# a.net
KiCad netlist of a schematic drawn in EAGLE
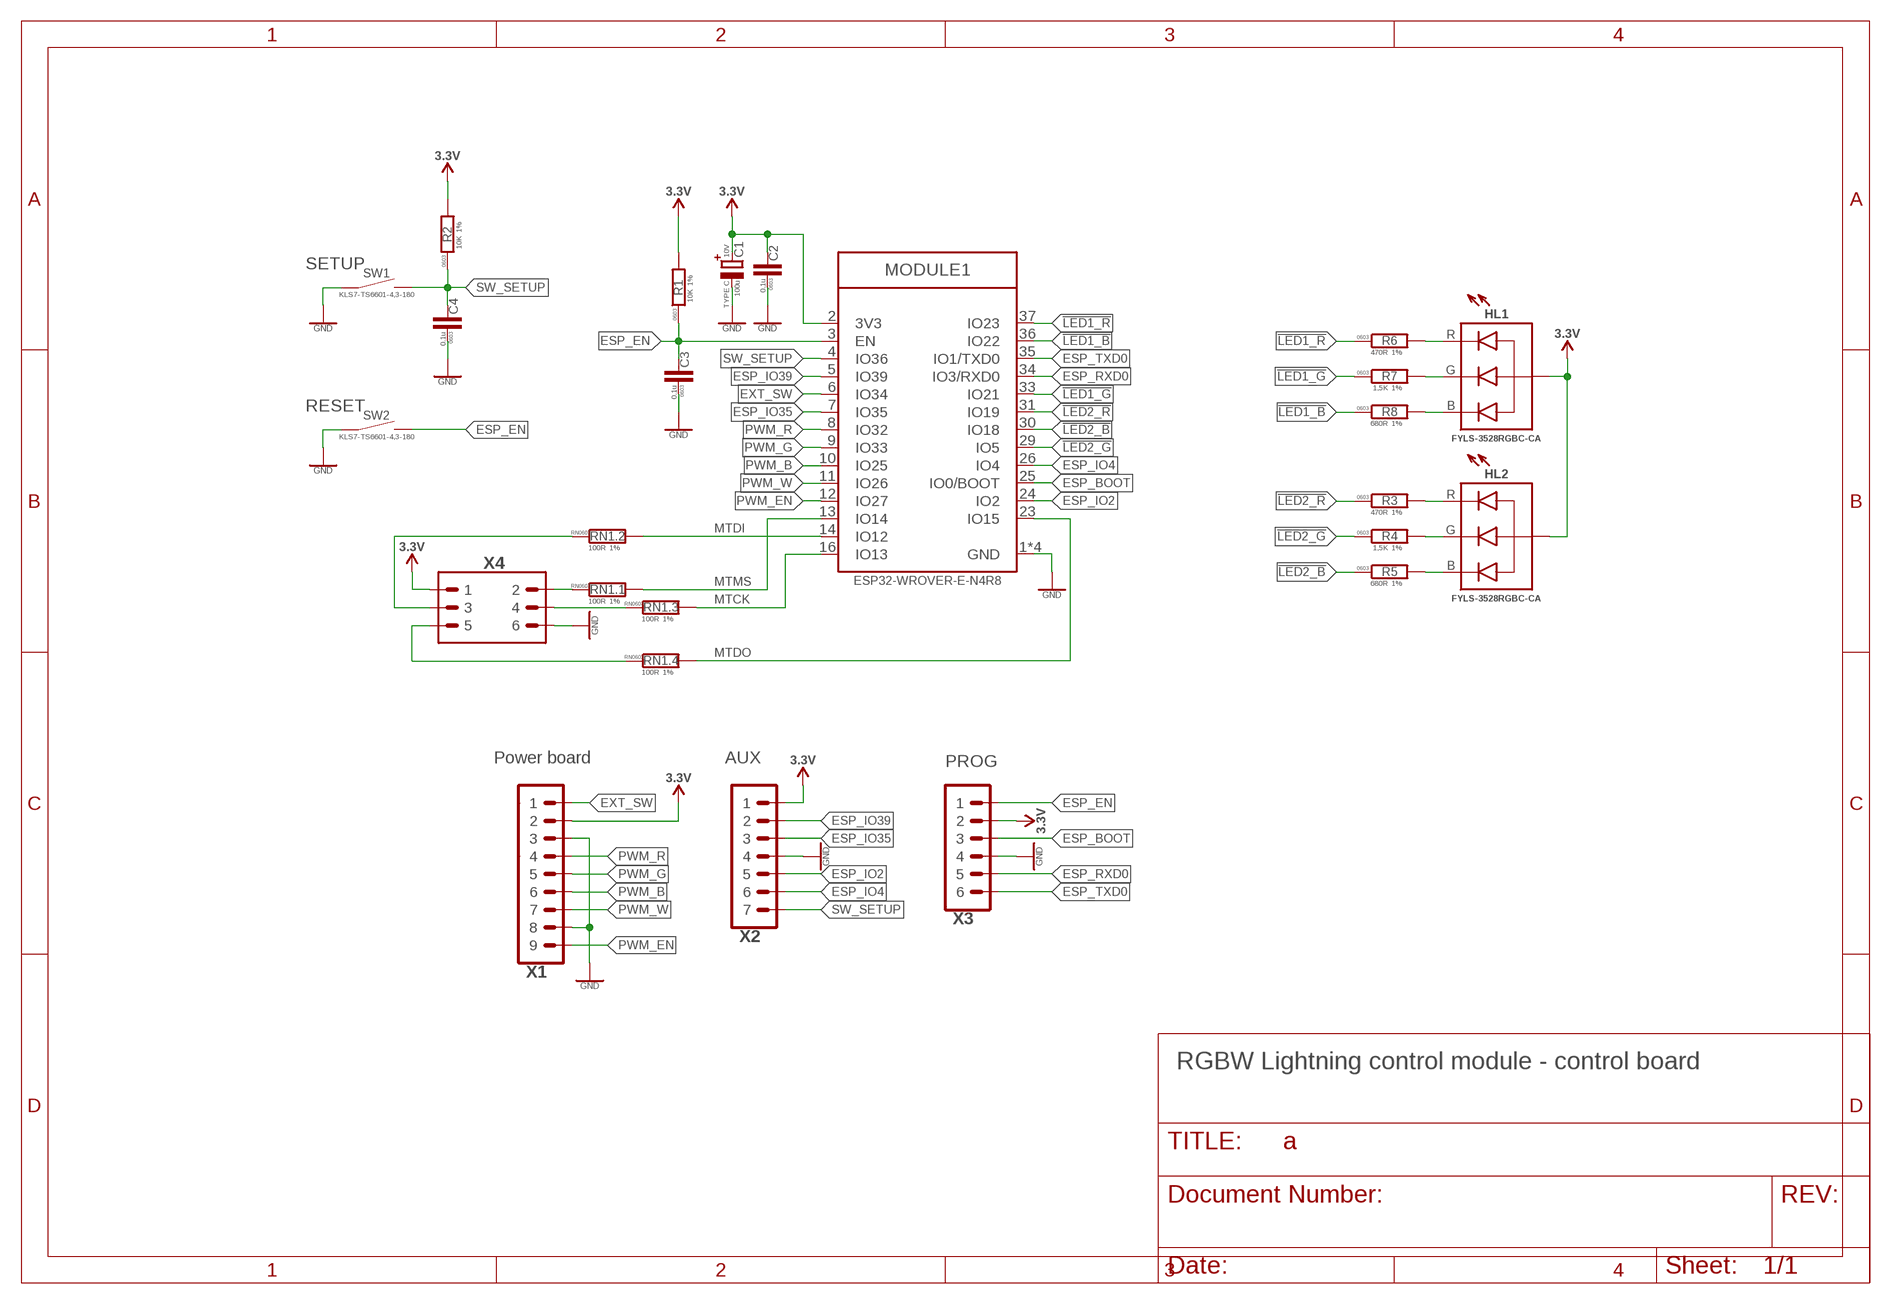
[diagram p0: schematic, sheet 1]

(export (version "E")
  (design (tool "Eeschema 10.0.6"))
  (components
    (comp (ref "C1")
      (value "100u")
      (footprint "eagle-import:CTANT_TYPE_C")
      (fields (field (name "PACKAGE") "TYPE C") (field (name "VOLTAGE") "10V"))
      (libsource (lib "eagle-import") (part "CPOL-TANT-TYPE-C"))
    )
    (comp (ref "C2")
      (value "0.1u")
      (footprint "eagle-import:C0603")
      (fields (field (name "PACKAGE") "0603"))
      (libsource (lib "eagle-import") (part "C-0603"))
    )
    (comp (ref "C3")
      (value "0.1u")
      (footprint "eagle-import:C0603")
      (fields (field (name "PACKAGE") "0603"))
      (libsource (lib "eagle-import") (part "C-0603"))
    )
    (comp (ref "C4")
      (value "0.1u")
      (footprint "eagle-import:C0603")
      (fields (field (name "PACKAGE") "0603"))
      (libsource (lib "eagle-import") (part "C-0603"))
    )
    (comp (ref "HL1")
      (value "LED_RGB-3528")
      (footprint "eagle-import:LED3528")
      (fields (field (name "MANF#") "FYLS-3528RGBC-CA") (field (name "MANF") "Foryard"))
      (libsource (lib "eagle-import") (part "LED_RGB-3528"))
    )
    (comp (ref "HL2")
      (value "LED_RGB-3528")
      (footprint "eagle-import:LED3528")
      (fields (field (name "MANF#") "FYLS-3528RGBC-CA") (field (name "MANF") "Foryard"))
      (libsource (lib "eagle-import") (part "LED_RGB-3528"))
    )
    (comp (ref "MODULE1")
      (value "ESP32-WROVER-(I)E")
      (footprint "eagle-import:ESP32-WROVER-E")
      (fields (field (name "MANF#") "ESP32-WROVER-E-N4R8") (field (name "MANF") "Espressif Systems"))
      (libsource (lib "eagle-import") (part "ESP32-WROVER-(I)E"))
    )
    (comp (ref "R1")
      (value "10K")
      (footprint "eagle-import:R0603")
      (fields (field (name "PACKAGE") "0603") (field (name "TOLERANCE") "1%"))
      (libsource (lib "eagle-import") (part "R-0603-1%"))
    )
    (comp (ref "R2")
      (value "10K")
      (footprint "eagle-import:R0603")
      (fields (field (name "PACKAGE") "0603") (field (name "TOLERANCE") "1%"))
      (libsource (lib "eagle-import") (part "R-0603-1%"))
    )
    (comp (ref "R3")
      (value "470R")
      (footprint "eagle-import:R0603")
      (fields (field (name "PACKAGE") "0603") (field (name "TOLERANCE") "1%"))
      (libsource (lib "eagle-import") (part "R-0603-1%"))
    )
    (comp (ref "R4")
      (value "1,5K")
      (footprint "eagle-import:R0603")
      (fields (field (name "PACKAGE") "0603") (field (name "TOLERANCE") "1%"))
      (libsource (lib "eagle-import") (part "R-0603-1%"))
    )
    (comp (ref "R5")
      (value "680R")
      (footprint "eagle-import:R0603")
      (fields (field (name "PACKAGE") "0603") (field (name "TOLERANCE") "1%"))
      (libsource (lib "eagle-import") (part "R-0603-1%"))
    )
    (comp (ref "R6")
      (value "470R")
      (footprint "eagle-import:R0603")
      (fields (field (name "PACKAGE") "0603") (field (name "TOLERANCE") "1%"))
      (libsource (lib "eagle-import") (part "R-0603-1%"))
    )
    (comp (ref "R7")
      (value "1,5K")
      (footprint "eagle-import:R0603")
      (fields (field (name "PACKAGE") "0603") (field (name "TOLERANCE") "1%"))
      (libsource (lib "eagle-import") (part "R-0603-1%"))
    )
    (comp (ref "R8")
      (value "680R")
      (footprint "eagle-import:R0603")
      (fields (field (name "PACKAGE") "0603") (field (name "TOLERANCE") "1%"))
      (libsource (lib "eagle-import") (part "R-0603-1%"))
    )
    (comp (ref "RN1")
      (value "100R")
      (footprint "eagle-import:R_4X0603")
      (fields (field (name "PACKAGE") "RN0603") (field (name "TOLERANCE") "1%"))
      (libsource (lib "eagle-import") (part "RN-0603-1%"))
    )
    (comp (ref "SW1")
      (value "TS6601-9,5")
      (footprint "eagle-import:SW4-6.0X6.0X5.0MM")
      (fields (field (name "MANF") "KLS"))
      (libsource (lib "eagle-import") (part "TACT_SWITCH-6X6-PTH"))
    )
    (comp (ref "SW2")
      (value "TS6601-9,5")
      (footprint "eagle-import:SW4-6.0X6.0X5.0MM")
      (fields (field (name "MANF") "KLS"))
      (libsource (lib "eagle-import") (part "TACT_SWITCH-6X6-PTH"))
    )
    (comp (ref "X1")
      (value "PINHEAD_1X09-2.54-TH-MALE")
      (footprint "eagle-import:1X09-PTH-2.54")
      (libsource (lib "eagle-import") (part "PINHEAD_1X09-2.54-TH-MALE"))
    )
    (comp (ref "X2")
      (value "PINHEAD_1X07-2.54")
      (footprint "eagle-import:1X07-PTH-2.54")
      (libsource (lib "eagle-import") (part "PINHEAD_1X07-2.54"))
    )
    (comp (ref "X3")
      (value "PINHEAD_1X06-2-MALE")
      (footprint "eagle-import:1X06-PTH-2")
      (libsource (lib "eagle-import") (part "PINHEAD_1X06-2-MALE"))
    )
    (comp (ref "X4")
      (value "PINHEAD_2X03-PTH-2.54")
      (footprint "eagle-import:2X03-PTH-2.54")
      (libsource (lib "eagle-import") (part "PINHEAD_2X03-PTH-2.54"))
    )
  )
  (nets
    (net (code "1") (name "/MTCK") (class "Default")
      (node (ref "MODULE1") (pin "16") (pinfunction "IO13_16") (pintype "tri_state"))
      (node (ref "RN1") (pin "6") (pinfunction "2_6") (pintype "passive"))
    )
    (net (code "2") (name "/MTDI") (class "Default")
      (node (ref "MODULE1") (pin "14") (pinfunction "IO12_14") (pintype "tri_state"))
      (node (ref "RN1") (pin "7") (pinfunction "2_7") (pintype "passive"))
    )
    (net (code "3") (name "/MTDO") (class "Default")
      (node (ref "MODULE1") (pin "23") (pinfunction "IO15_23") (pintype "tri_state"))
      (node (ref "RN1") (pin "5") (pinfunction "2_5") (pintype "passive"))
    )
    (net (code "4") (name "/MTMS") (class "Default")
      (node (ref "MODULE1") (pin "13") (pinfunction "IO14_13") (pintype "tri_state"))
      (node (ref "RN1") (pin "8") (pinfunction "2_8") (pintype "passive"))
    )
    (net (code "5") (name "/~{LED1_B}") (class "Default")
      (node (ref "MODULE1") (pin "36") (pinfunction "IO22_36") (pintype "tri_state"))
      (node (ref "R8") (pin "1") (pinfunction "1_1") (pintype "passive"))
    )
    (net (code "6") (name "/~{LED1_G}") (class "Default")
      (node (ref "MODULE1") (pin "33") (pinfunction "IO21_33") (pintype "tri_state"))
      (node (ref "R7") (pin "1") (pinfunction "1_1") (pintype "passive"))
    )
    (net (code "7") (name "/~{LED1_R}") (class "Default")
      (node (ref "MODULE1") (pin "37") (pinfunction "IO23_37") (pintype "tri_state"))
      (node (ref "R6") (pin "1") (pinfunction "1_1") (pintype "passive"))
    )
    (net (code "8") (name "/~{LED2_B}") (class "Default")
      (node (ref "MODULE1") (pin "30") (pinfunction "IO18_30") (pintype "tri_state"))
      (node (ref "R5") (pin "1") (pinfunction "1_1") (pintype "passive"))
    )
    (net (code "9") (name "/~{LED2_G}") (class "Default")
      (node (ref "MODULE1") (pin "29") (pinfunction "IO5_29") (pintype "tri_state"))
      (node (ref "R4") (pin "1") (pinfunction "1_1") (pintype "passive"))
    )
    (net (code "10") (name "/~{LED2_R}") (class "Default")
      (node (ref "MODULE1") (pin "31") (pinfunction "IO19_31") (pintype "tri_state"))
      (node (ref "R3") (pin "1") (pinfunction "1_1") (pintype "passive"))
    )
    (net (code "11") (name "3.3V") (class "Default")
      (node (ref "C1") (pin "+") (pinfunction "+_+") (pintype "passive"))
      (node (ref "C2") (pin "2") (pinfunction "2_2") (pintype "passive"))
      (node (ref "HL1") (pin "2") (pinfunction "A_2") (pintype "bidirectional"))
      (node (ref "HL2") (pin "2") (pinfunction "A_2") (pintype "bidirectional"))
      (node (ref "MODULE1") (pin "2") (pinfunction "3V3_2") (pintype "passive"))
      (node (ref "R1") (pin "2") (pinfunction "2_2") (pintype "passive"))
      (node (ref "R2") (pin "2") (pinfunction "2_2") (pintype "passive"))
      (node (ref "X1") (pin "2") (pinfunction "2_2") (pintype "passive"))
      (node (ref "X2") (pin "1") (pinfunction "1_1") (pintype "passive"))
      (node (ref "X3") (pin "2") (pinfunction "2_2") (pintype "passive"))
      (node (ref "X4") (pin "1") (pinfunction "1_1") (pintype "passive"))
    )
    (net (code "12") (name "ESP_BOOT") (class "Default")
      (node (ref "MODULE1") (pin "25") (pinfunction "IO0/BOOT_25") (pintype "tri_state"))
      (node (ref "X3") (pin "3") (pinfunction "3_3") (pintype "passive"))
    )
    (net (code "13") (name "ESP_EN") (class "Default")
      (node (ref "C3") (pin "2") (pinfunction "2_2") (pintype "passive"))
      (node (ref "MODULE1") (pin "3") (pinfunction "EN_3") (pintype "tri_state"))
      (node (ref "R1") (pin "1") (pinfunction "1_1") (pintype "passive"))
      (node (ref "SW2") (pin "2") (pinfunction "2_2") (pintype "bidirectional"))
      (node (ref "SW2") (pin "3") (pinfunction "2_3") (pintype "bidirectional"))
      (node (ref "X3") (pin "1") (pinfunction "1_1") (pintype "passive"))
    )
    (net (code "14") (name "ESP_IO2") (class "Default")
      (node (ref "MODULE1") (pin "24") (pinfunction "IO2_24") (pintype "tri_state"))
      (node (ref "X2") (pin "5") (pinfunction "5_5") (pintype "passive"))
    )
    (net (code "15") (name "ESP_IO4") (class "Default")
      (node (ref "MODULE1") (pin "26") (pinfunction "IO4_26") (pintype "tri_state"))
      (node (ref "X2") (pin "6") (pinfunction "6_6") (pintype "passive"))
    )
    (net (code "16") (name "ESP_IO35") (class "Default")
      (node (ref "MODULE1") (pin "7") (pinfunction "IO35_7") (pintype "tri_state"))
      (node (ref "X2") (pin "3") (pinfunction "3_3") (pintype "passive"))
    )
    (net (code "17") (name "ESP_IO39") (class "Default")
      (node (ref "MODULE1") (pin "5") (pinfunction "IO39_5") (pintype "tri_state"))
      (node (ref "X2") (pin "2") (pinfunction "2_2") (pintype "passive"))
    )
    (net (code "18") (name "ESP_RXD0") (class "Default")
      (node (ref "MODULE1") (pin "34") (pinfunction "IO3/RXD0_34") (pintype "tri_state"))
      (node (ref "X3") (pin "5") (pinfunction "5_5") (pintype "passive"))
    )
    (net (code "19") (name "ESP_TXD0") (class "Default")
      (node (ref "MODULE1") (pin "35") (pinfunction "IO1/TXD0_35") (pintype "tri_state"))
      (node (ref "X3") (pin "6") (pinfunction "6_6") (pintype "passive"))
    )
    (net (code "20") (name "EXT_SW") (class "Default")
      (node (ref "MODULE1") (pin "6") (pinfunction "IO34_6") (pintype "tri_state"))
      (node (ref "X1") (pin "1") (pinfunction "1_1") (pintype "passive"))
    )
    (net (code "21") (name "GND") (class "Default")
      (node (ref "C1") (pin "-") (pinfunction "-_-") (pintype "passive"))
      (node (ref "C2") (pin "1") (pinfunction "1_1") (pintype "passive"))
      (node (ref "C3") (pin "1") (pinfunction "1_1") (pintype "passive"))
      (node (ref "C4") (pin "1") (pinfunction "1_1") (pintype "passive"))
      (node (ref "MODULE1") (pin "1") (pinfunction "GND_1") (pintype "tri_state"))
      (node (ref "MODULE1") (pin "15") (pinfunction "GND_15") (pintype "tri_state"))
      (node (ref "MODULE1") (pin "38") (pinfunction "GND_38") (pintype "tri_state"))
      (node (ref "MODULE1") (pin "39") (pinfunction "GND_39") (pintype "tri_state"))
      (node (ref "SW1") (pin "1") (pinfunction "1_1") (pintype "bidirectional"))
      (node (ref "SW1") (pin "4") (pinfunction "1_4") (pintype "bidirectional"))
      (node (ref "SW2") (pin "1") (pinfunction "1_1") (pintype "bidirectional"))
      (node (ref "SW2") (pin "4") (pinfunction "1_4") (pintype "bidirectional"))
      (node (ref "X1") (pin "3") (pinfunction "3_3") (pintype "passive"))
      (node (ref "X1") (pin "8") (pinfunction "8_8") (pintype "passive"))
      (node (ref "X2") (pin "4") (pinfunction "4_4") (pintype "passive"))
      (node (ref "X3") (pin "4") (pinfunction "4_4") (pintype "passive"))
      (node (ref "X4") (pin "6") (pinfunction "6_6") (pintype "passive"))
    )
    (net (code "22") (name "Net-(HL1-B)") (class "Default")
      (node (ref "HL1") (pin "3") (pinfunction "B_3") (pintype "bidirectional"))
      (node (ref "R8") (pin "2") (pinfunction "2_2") (pintype "passive"))
    )
    (net (code "23") (name "Net-(HL1-G)") (class "Default")
      (node (ref "HL1") (pin "4") (pinfunction "G_4") (pintype "bidirectional"))
      (node (ref "R7") (pin "2") (pinfunction "2_2") (pintype "passive"))
    )
    (net (code "24") (name "Net-(HL1-R)") (class "Default")
      (node (ref "HL1") (pin "1") (pinfunction "R_1") (pintype "bidirectional"))
      (node (ref "R6") (pin "2") (pinfunction "2_2") (pintype "passive"))
    )
    (net (code "25") (name "Net-(HL2-B)") (class "Default")
      (node (ref "HL2") (pin "3") (pinfunction "B_3") (pintype "bidirectional"))
      (node (ref "R5") (pin "2") (pinfunction "2_2") (pintype "passive"))
    )
    (net (code "26") (name "Net-(HL2-G)") (class "Default")
      (node (ref "HL2") (pin "4") (pinfunction "G_4") (pintype "bidirectional"))
      (node (ref "R4") (pin "2") (pinfunction "2_2") (pintype "passive"))
    )
    (net (code "27") (name "Net-(HL2-R)") (class "Default")
      (node (ref "HL2") (pin "1") (pinfunction "R_1") (pintype "bidirectional"))
      (node (ref "R3") (pin "2") (pinfunction "2_2") (pintype "passive"))
    )
    (net (code "28") (name "Net-(RN1-Pad1)") (class "Default")
      (node (ref "RN1") (pin "1") (pinfunction "1_1") (pintype "passive"))
      (node (ref "X4") (pin "2") (pinfunction "2_2") (pintype "passive"))
    )
    (net (code "29") (name "Net-(RN1B-1)") (class "Default")
      (node (ref "RN1") (pin "2") (pinfunction "1_2") (pintype "passive"))
      (node (ref "X4") (pin "3") (pinfunction "3_3") (pintype "passive"))
    )
    (net (code "30") (name "Net-(RN1C-1)") (class "Default")
      (node (ref "RN1") (pin "3") (pinfunction "1_3") (pintype "passive"))
      (node (ref "X4") (pin "4") (pinfunction "4_4") (pintype "passive"))
    )
    (net (code "31") (name "Net-(RN1D-1)") (class "Default")
      (node (ref "RN1") (pin "4") (pinfunction "1_4") (pintype "passive"))
      (node (ref "X4") (pin "5") (pinfunction "5_5") (pintype "passive"))
    )
    (net (code "32") (name "PWM_B") (class "Default")
      (node (ref "MODULE1") (pin "10") (pinfunction "IO25_10") (pintype "tri_state"))
      (node (ref "X1") (pin "6") (pinfunction "6_6") (pintype "passive"))
    )
    (net (code "33") (name "PWM_EN") (class "Default")
      (node (ref "MODULE1") (pin "12") (pinfunction "IO27_12") (pintype "tri_state"))
      (node (ref "X1") (pin "9") (pinfunction "9_9") (pintype "passive"))
    )
    (net (code "34") (name "PWM_G") (class "Default")
      (node (ref "MODULE1") (pin "9") (pinfunction "IO33_9") (pintype "tri_state"))
      (node (ref "X1") (pin "5") (pinfunction "5_5") (pintype "passive"))
    )
    (net (code "35") (name "PWM_R") (class "Default")
      (node (ref "MODULE1") (pin "8") (pinfunction "IO32_8") (pintype "tri_state"))
      (node (ref "X1") (pin "4") (pinfunction "4_4") (pintype "passive"))
    )
    (net (code "36") (name "PWM_W") (class "Default")
      (node (ref "MODULE1") (pin "11") (pinfunction "IO26_11") (pintype "tri_state"))
      (node (ref "X1") (pin "7") (pinfunction "7_7") (pintype "passive"))
    )
    (net (code "37") (name "SW_SETUP") (class "Default")
      (node (ref "C4") (pin "2") (pinfunction "2_2") (pintype "passive"))
      (node (ref "MODULE1") (pin "4") (pinfunction "IO36_4") (pintype "tri_state"))
      (node (ref "R2") (pin "1") (pinfunction "1_1") (pintype "passive"))
      (node (ref "SW1") (pin "2") (pinfunction "2_2") (pintype "bidirectional"))
      (node (ref "SW1") (pin "3") (pinfunction "2_3") (pintype "bidirectional"))
      (node (ref "X2") (pin "7") (pinfunction "7_7") (pintype "passive"))
    )
  )
)
